# FPGA_NonIO.net
KiCad netlist of a schematic drawn in Altium Designer
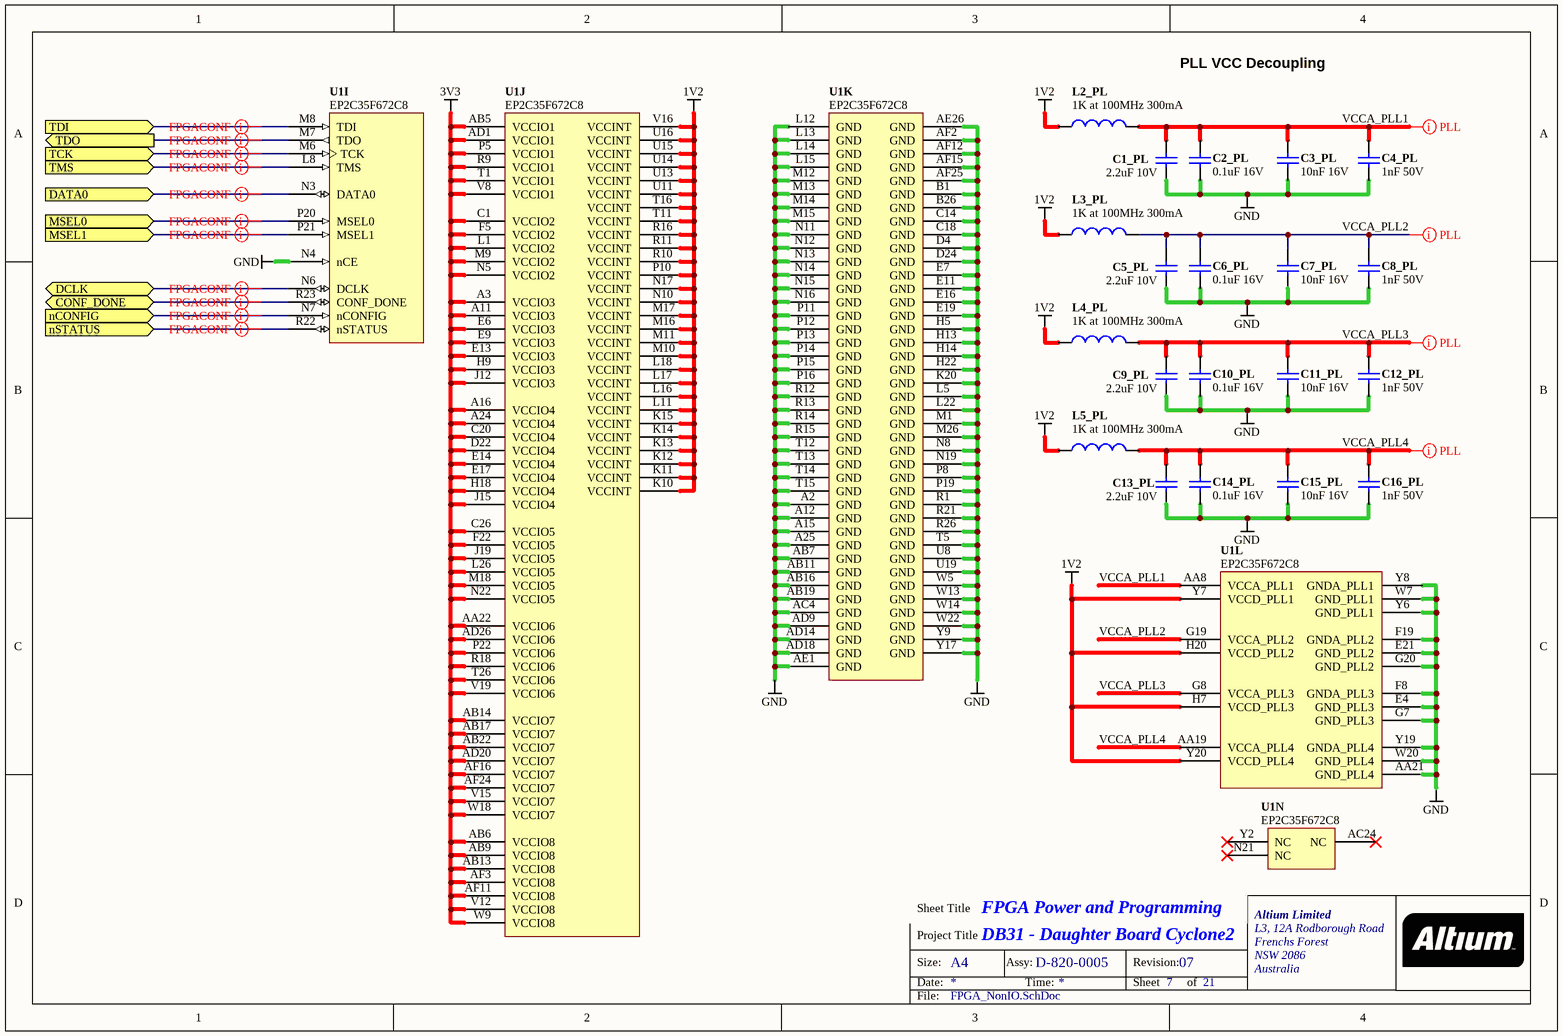
[diagram p0: FPGA_NonIO.SchDoc]

(export (version "E")
  (design (tool "Eeschema 10.0.6"))
  (components
    (comp (ref "C1_PL")
      (value "2.2uF 10V")
      (footprint "CAPC1608-STAR")
      (description "Capacitor, Ceramic, 2.2uF 10% 10V 0603 (1608) X5R")
      (fields (field (name "TOLERANCE") "10 %"))
      (libsource (lib "AltiumDesignLibrary") (part "CAP-NP"))
    )
    (comp (ref "C2_PL")
      (value "0.1uF 16V")
      (footprint "CAPC1005-STAR")
      (description "Capacitor, Ceramic, 0.1uF 10% 16V 0402 (1005) X7R")
      (fields (field (name "TOLERANCE") "10 %"))
      (libsource (lib "AltiumDesignLibrary") (part "CAP-NP"))
    )
    (comp (ref "C3_PL")
      (value "10nF 16V")
      (footprint "CAPC1005-STAR")
      (description "Capacitor, Ceramic, 10nF 10% 16V 0402 (1005) X7R")
      (fields (field (name "TOLERANCE") "10 %"))
      (libsource (lib "AltiumDesignLibrary") (part "CAP-NP"))
    )
    (comp (ref "C4_PL")
      (value "1nF 50V")
      (footprint "CAPC1005-STAR")
      (description "Capacitor, Ceramic, 1nF 10% 50V 0402 (1005) X7R")
      (fields (field (name "TOLERANCE") "10 %"))
      (libsource (lib "AltiumDesignLibrary") (part "CAP-NP"))
    )
    (comp (ref "C5_PL")
      (value "2.2uF 10V")
      (footprint "CAPC1608-STAR")
      (description "Capacitor, Ceramic, 2.2uF 10% 10V 0603 (1608) X5R")
      (fields (field (name "TOLERANCE") "10 %"))
      (libsource (lib "AltiumDesignLibrary") (part "CAP-NP"))
    )
    (comp (ref "C6_PL")
      (value "0.1uF 16V")
      (footprint "CAPC1005-STAR")
      (description "Capacitor, Ceramic, 0.1uF 10% 16V 0402 (1005) X7R")
      (fields (field (name "TOLERANCE") "10 %"))
      (libsource (lib "AltiumDesignLibrary") (part "CAP-NP"))
    )
    (comp (ref "C7_PL")
      (value "10nF 16V")
      (footprint "CAPC1005-STAR")
      (description "Capacitor, Ceramic, 10nF 10% 16V 0402 (1005) X7R")
      (fields (field (name "TOLERANCE") "10 %"))
      (libsource (lib "AltiumDesignLibrary") (part "CAP-NP"))
    )
    (comp (ref "C8_PL")
      (value "1nF 50V")
      (footprint "CAPC1005-STAR")
      (description "Capacitor, Ceramic, 1nF 10% 50V 0402 (1005) X7R")
      (fields (field (name "TOLERANCE") "10 %"))
      (libsource (lib "AltiumDesignLibrary") (part "CAP-NP"))
    )
    (comp (ref "C9_PL")
      (value "2.2uF 10V")
      (footprint "CAPC1608-STAR")
      (description "Capacitor, Ceramic, 2.2uF 10% 10V 0603 (1608) X5R")
      (fields (field (name "TOLERANCE") "10 %"))
      (libsource (lib "AltiumDesignLibrary") (part "CAP-NP"))
    )
    (comp (ref "C10_PL")
      (value "0.1uF 16V")
      (footprint "CAPC1005-STAR")
      (description "Capacitor, Ceramic, 0.1uF 10% 16V 0402 (1005) X7R")
      (fields (field (name "TOLERANCE") "10 %"))
      (libsource (lib "AltiumDesignLibrary") (part "CAP-NP"))
    )
    (comp (ref "C11_PL")
      (value "10nF 16V")
      (footprint "CAPC1005-STAR")
      (description "Capacitor, Ceramic, 10nF 10% 16V 0402 (1005) X7R")
      (fields (field (name "TOLERANCE") "10 %"))
      (libsource (lib "AltiumDesignLibrary") (part "CAP-NP"))
    )
    (comp (ref "C12_PL")
      (value "1nF 50V")
      (footprint "CAPC1005-STAR")
      (description "Capacitor, Ceramic, 1nF 10% 50V 0402 (1005) X7R")
      (fields (field (name "TOLERANCE") "10 %"))
      (libsource (lib "AltiumDesignLibrary") (part "CAP-NP"))
    )
    (comp (ref "C13_PL")
      (value "2.2uF 10V")
      (footprint "CAPC1608-STAR")
      (description "Capacitor, Ceramic, 2.2uF 10% 10V 0603 (1608) X5R")
      (fields (field (name "TOLERANCE") "10 %"))
      (libsource (lib "AltiumDesignLibrary") (part "CAP-NP"))
    )
    (comp (ref "C14_PL")
      (value "0.1uF 16V")
      (footprint "CAPC1005-STAR")
      (description "Capacitor, Ceramic, 0.1uF 10% 16V 0402 (1005) X7R")
      (fields (field (name "TOLERANCE") "10 %"))
      (libsource (lib "AltiumDesignLibrary") (part "CAP-NP"))
    )
    (comp (ref "C15_PL")
      (value "10nF 16V")
      (footprint "CAPC1005-STAR")
      (description "Capacitor, Ceramic, 10nF 10% 16V 0402 (1005) X7R")
      (fields (field (name "TOLERANCE") "10 %"))
      (libsource (lib "AltiumDesignLibrary") (part "CAP-NP"))
    )
    (comp (ref "C16_PL")
      (value "1nF 50V")
      (footprint "CAPC1005-STAR")
      (description "Capacitor, Ceramic, 1nF 10% 50V 0402 (1005) X7R")
      (fields (field (name "TOLERANCE") "10 %"))
      (libsource (lib "AltiumDesignLibrary") (part "CAP-NP"))
    )
    (comp (ref "L2_PL")
      (value "1K at 100MHz 300mA")
      (footprint "INDC2012-STAR")
      (description "Inductor, Ferrite Bead 1K@100MHz 300mA 0805 (2012) BMB2A1000LN2")
      (libsource (lib "AltiumDesignLibrary") (part "IND-FER"))
    )
    (comp (ref "L3_PL")
      (value "1K at 100MHz 300mA")
      (footprint "INDC2012-STAR")
      (description "Inductor, Ferrite Bead 1K@100MHz 300mA 0805 (2012) BMB2A1000LN2")
      (libsource (lib "AltiumDesignLibrary") (part "IND-FER"))
    )
    (comp (ref "L4_PL")
      (value "1K at 100MHz 300mA")
      (footprint "INDC2012-STAR")
      (description "Inductor, Ferrite Bead 1K@100MHz 300mA 0805 (2012) BMB2A1000LN2")
      (libsource (lib "AltiumDesignLibrary") (part "IND-FER"))
    )
    (comp (ref "L5_PL")
      (value "1K at 100MHz 300mA")
      (footprint "INDC2012-STAR")
      (description "Inductor, Ferrite Bead 1K@100MHz 300mA 0805 (2012) BMB2A1000LN2")
      (libsource (lib "AltiumDesignLibrary") (part "IND-FER"))
    )
    (comp (ref "U1")
      (value "EP2C35F672C8")
      (footprint "BGA100P26X26-672")
      (description "FPGA, Altera Cyclone2-35 F672")
      (libsource (lib "AltiumDesignLibrary") (part "EP2C35F672C8"))
    )
  )
  (nets
    (net (code "1") (name "/CONF_DONE") (class "Default")
      (node (ref "U1") (pin "R23") (pinfunction "CONF_DONE_R23") (pintype "bidirectional"))
    )
    (net (code "2") (name "/DATA0") (class "Default")
      (node (ref "U1") (pin "N3") (pinfunction "DATA0_N3") (pintype "bidirectional"))
    )
    (net (code "3") (name "/DCLK") (class "Default")
      (node (ref "U1") (pin "N6") (pinfunction "DCLK_N6") (pintype "bidirectional"))
    )
    (net (code "4") (name "/MSEL0") (class "Default")
      (node (ref "U1") (pin "P20") (pinfunction "MSEL0_P20") (pintype "input"))
    )
    (net (code "5") (name "/MSEL1") (class "Default")
      (node (ref "U1") (pin "P21") (pinfunction "MSEL1_P21") (pintype "input"))
    )
    (net (code "6") (name "/TCK") (class "Default")
      (node (ref "U1") (pin "M6") (pinfunction "TCK_M6") (pintype "input"))
    )
    (net (code "7") (name "/TDI") (class "Default")
      (node (ref "U1") (pin "M8") (pinfunction "TDI_M8") (pintype "input"))
    )
    (net (code "8") (name "/TDO") (class "Default")
      (node (ref "U1") (pin "M7") (pinfunction "TDO_M7") (pintype "output"))
    )
    (net (code "9") (name "/TMS") (class "Default")
      (node (ref "U1") (pin "L8") (pinfunction "TMS_L8") (pintype "input"))
    )
    (net (code "10") (name "/VCCA_PLL1") (class "Default")
      (node (ref "C1_PL") (pin "1") (pinfunction "1_1") (pintype "passive"))
      (node (ref "C2_PL") (pin "1") (pinfunction "1_1") (pintype "passive"))
      (node (ref "C3_PL") (pin "1") (pinfunction "1_1") (pintype "passive"))
      (node (ref "C4_PL") (pin "1") (pinfunction "1_1") (pintype "passive"))
      (node (ref "L2_PL") (pin "2") (pinfunction "2_2") (pintype "passive"))
      (node (ref "U1") (pin "AA8") (pinfunction "VCCA_PLL1_AA8") (pintype "power_in"))
    )
    (net (code "11") (name "/VCCA_PLL2") (class "Default")
      (node (ref "C5_PL") (pin "1") (pinfunction "1_1") (pintype "passive"))
      (node (ref "C6_PL") (pin "1") (pinfunction "1_1") (pintype "passive"))
      (node (ref "C7_PL") (pin "1") (pinfunction "1_1") (pintype "passive"))
      (node (ref "C8_PL") (pin "1") (pinfunction "1_1") (pintype "passive"))
      (node (ref "L3_PL") (pin "2") (pinfunction "2_2") (pintype "passive"))
      (node (ref "U1") (pin "G19") (pinfunction "VCCA_PLL2_G19") (pintype "power_in"))
    )
    (net (code "12") (name "/VCCA_PLL3") (class "Default")
      (node (ref "C10_PL") (pin "1") (pinfunction "1_1") (pintype "passive"))
      (node (ref "C11_PL") (pin "1") (pinfunction "1_1") (pintype "passive"))
      (node (ref "C12_PL") (pin "1") (pinfunction "1_1") (pintype "passive"))
      (node (ref "C9_PL") (pin "1") (pinfunction "1_1") (pintype "passive"))
      (node (ref "L4_PL") (pin "2") (pinfunction "2_2") (pintype "passive"))
      (node (ref "U1") (pin "G8") (pinfunction "VCCA_PLL3_G8") (pintype "power_in"))
    )
    (net (code "13") (name "/VCCA_PLL4") (class "Default")
      (node (ref "C13_PL") (pin "1") (pinfunction "1_1") (pintype "passive"))
      (node (ref "C14_PL") (pin "1") (pinfunction "1_1") (pintype "passive"))
      (node (ref "C15_PL") (pin "1") (pinfunction "1_1") (pintype "passive"))
      (node (ref "C16_PL") (pin "1") (pinfunction "1_1") (pintype "passive"))
      (node (ref "L5_PL") (pin "2") (pinfunction "2_2") (pintype "passive"))
      (node (ref "U1") (pin "AA19") (pinfunction "VCCA_PLL4_AA19") (pintype "power_in"))
    )
    (net (code "14") (name "/nCONFIG") (class "Default")
      (node (ref "U1") (pin "N7") (pinfunction "nCONFIG_N7") (pintype "input"))
    )
    (net (code "15") (name "/nSTATUS") (class "Default")
      (node (ref "U1") (pin "R22") (pinfunction "nSTATUS_R22") (pintype "bidirectional"))
    )
    (net (code "16") (name "1V2") (class "Default")
      (node (ref "L2_PL") (pin "1") (pinfunction "1_1") (pintype "passive"))
      (node (ref "L3_PL") (pin "1") (pinfunction "1_1") (pintype "passive"))
      (node (ref "L4_PL") (pin "1") (pinfunction "1_1") (pintype "passive"))
      (node (ref "L5_PL") (pin "1") (pinfunction "1_1") (pintype "passive"))
      (node (ref "U1") (pin "H20") (pinfunction "VCCD_PLL2_H20") (pintype "power_in"))
      (node (ref "U1") (pin "H7") (pinfunction "VCCD_PLL3_H7") (pintype "power_in"))
      (node (ref "U1") (pin "K10") (pinfunction "VCCINT_K10") (pintype "power_in"))
      (node (ref "U1") (pin "K11") (pinfunction "VCCINT_K11") (pintype "power_in"))
      (node (ref "U1") (pin "K12") (pinfunction "VCCINT_K12") (pintype "power_in"))
      (node (ref "U1") (pin "K13") (pinfunction "VCCINT_K13") (pintype "power_in"))
      (node (ref "U1") (pin "K14") (pinfunction "VCCINT_K14") (pintype "power_in"))
      (node (ref "U1") (pin "K15") (pinfunction "VCCINT_K15") (pintype "power_in"))
      (node (ref "U1") (pin "L11") (pinfunction "VCCINT_L11") (pintype "power_in"))
      (node (ref "U1") (pin "L16") (pinfunction "VCCINT_L16") (pintype "power_in"))
      (node (ref "U1") (pin "L17") (pinfunction "VCCINT_L17") (pintype "power_in"))
      (node (ref "U1") (pin "L18") (pinfunction "VCCINT_L18") (pintype "power_in"))
      (node (ref "U1") (pin "M10") (pinfunction "VCCINT_M10") (pintype "power_in"))
      (node (ref "U1") (pin "M11") (pinfunction "VCCINT_M11") (pintype "power_in"))
      (node (ref "U1") (pin "M16") (pinfunction "VCCINT_M16") (pintype "power_in"))
      (node (ref "U1") (pin "M17") (pinfunction "VCCINT_M17") (pintype "power_in"))
      (node (ref "U1") (pin "N10") (pinfunction "VCCINT_N10") (pintype "power_in"))
      (node (ref "U1") (pin "N17") (pinfunction "VCCINT_N17") (pintype "power_in"))
      (node (ref "U1") (pin "P10") (pinfunction "VCCINT_P10") (pintype "power_in"))
      (node (ref "U1") (pin "R10") (pinfunction "VCCINT_R10") (pintype "power_in"))
      (node (ref "U1") (pin "R11") (pinfunction "VCCINT_R11") (pintype "power_in"))
      (node (ref "U1") (pin "R16") (pinfunction "VCCINT_R16") (pintype "power_in"))
      (node (ref "U1") (pin "T11") (pinfunction "VCCINT_T11") (pintype "power_in"))
      (node (ref "U1") (pin "T16") (pinfunction "VCCINT_T16") (pintype "power_in"))
      (node (ref "U1") (pin "U11") (pinfunction "VCCINT_U11") (pintype "power_in"))
      (node (ref "U1") (pin "U13") (pinfunction "VCCINT_U13") (pintype "power_in"))
      (node (ref "U1") (pin "U14") (pinfunction "VCCINT_U14") (pintype "power_in"))
      (node (ref "U1") (pin "U15") (pinfunction "VCCINT_U15") (pintype "power_in"))
      (node (ref "U1") (pin "U16") (pinfunction "VCCINT_U16") (pintype "power_in"))
      (node (ref "U1") (pin "V16") (pinfunction "VCCINT_V16") (pintype "power_in"))
      (node (ref "U1") (pin "Y20") (pinfunction "VCCD_PLL4_Y20") (pintype "power_in"))
      (node (ref "U1") (pin "Y7") (pinfunction "VCCD_PLL1_Y7") (pintype "power_in"))
    )
    (net (code "17") (name "3V3") (class "Default")
      (node (ref "U1") (pin "A11") (pinfunction "VCCIO3_A11") (pintype "power_in"))
      (node (ref "U1") (pin "A16") (pinfunction "VCCIO4_A16") (pintype "power_in"))
      (node (ref "U1") (pin "A24") (pinfunction "VCCIO4_A24") (pintype "power_in"))
      (node (ref "U1") (pin "A3") (pinfunction "VCCIO3_A3") (pintype "power_in"))
      (node (ref "U1") (pin "AA22") (pinfunction "VCCIO6_AA22") (pintype "power_in"))
      (node (ref "U1") (pin "AB13") (pinfunction "VCCIO8_AB13") (pintype "power_in"))
      (node (ref "U1") (pin "AB14") (pinfunction "VCCIO7_AB14") (pintype "power_in"))
      (node (ref "U1") (pin "AB17") (pinfunction "VCCIO7_AB17") (pintype "power_in"))
      (node (ref "U1") (pin "AB22") (pinfunction "VCCIO7_AB22") (pintype "power_in"))
      (node (ref "U1") (pin "AB5") (pinfunction "VCCIO1_AB5") (pintype "power_in"))
      (node (ref "U1") (pin "AB6") (pinfunction "VCCIO8_AB6") (pintype "power_in"))
      (node (ref "U1") (pin "AB9") (pinfunction "VCCIO8_AB9") (pintype "power_in"))
      (node (ref "U1") (pin "AD1") (pinfunction "VCCIO1_AD1") (pintype "power_in"))
      (node (ref "U1") (pin "AD20") (pinfunction "VCCIO7_AD20") (pintype "power_in"))
      (node (ref "U1") (pin "AD26") (pinfunction "VCCIO6_AD26") (pintype "power_in"))
      (node (ref "U1") (pin "AF11") (pinfunction "VCCIO8_AF11") (pintype "power_in"))
      (node (ref "U1") (pin "AF16") (pinfunction "VCCIO7_AF16") (pintype "power_in"))
      (node (ref "U1") (pin "AF24") (pinfunction "VCCIO7_AF24") (pintype "power_in"))
      (node (ref "U1") (pin "AF3") (pinfunction "VCCIO8_AF3") (pintype "power_in"))
      (node (ref "U1") (pin "C1") (pinfunction "VCCIO2_C1") (pintype "power_in"))
      (node (ref "U1") (pin "C20") (pinfunction "VCCIO4_C20") (pintype "power_in"))
      (node (ref "U1") (pin "C26") (pinfunction "VCCIO5_C26") (pintype "power_in"))
      (node (ref "U1") (pin "D22") (pinfunction "VCCIO4_D22") (pintype "power_in"))
      (node (ref "U1") (pin "E13") (pinfunction "VCCIO3_E13") (pintype "power_in"))
      (node (ref "U1") (pin "E14") (pinfunction "VCCIO4_E14") (pintype "power_in"))
      (node (ref "U1") (pin "E17") (pinfunction "VCCIO4_E17") (pintype "power_in"))
      (node (ref "U1") (pin "E6") (pinfunction "VCCIO3_E6") (pintype "power_in"))
      (node (ref "U1") (pin "E9") (pinfunction "VCCIO3_E9") (pintype "power_in"))
      (node (ref "U1") (pin "F22") (pinfunction "VCCIO5_F22") (pintype "power_in"))
      (node (ref "U1") (pin "F5") (pinfunction "VCCIO2_F5") (pintype "power_in"))
      (node (ref "U1") (pin "H18") (pinfunction "VCCIO4_H18") (pintype "power_in"))
      (node (ref "U1") (pin "H9") (pinfunction "VCCIO3_H9") (pintype "power_in"))
      (node (ref "U1") (pin "J12") (pinfunction "VCCIO3_J12") (pintype "power_in"))
      (node (ref "U1") (pin "J15") (pinfunction "VCCIO4_J15") (pintype "power_in"))
      (node (ref "U1") (pin "J19") (pinfunction "VCCIO5_J19") (pintype "power_in"))
      (node (ref "U1") (pin "L1") (pinfunction "VCCIO2_L1") (pintype "power_in"))
      (node (ref "U1") (pin "L26") (pinfunction "VCCIO5_L26") (pintype "power_in"))
      (node (ref "U1") (pin "M18") (pinfunction "VCCIO5_M18") (pintype "power_in"))
      (node (ref "U1") (pin "M9") (pinfunction "VCCIO2_M9") (pintype "power_in"))
      (node (ref "U1") (pin "N22") (pinfunction "VCCIO5_N22") (pintype "power_in"))
      (node (ref "U1") (pin "N5") (pinfunction "VCCIO2_N5") (pintype "power_in"))
      (node (ref "U1") (pin "P22") (pinfunction "VCCIO6_P22") (pintype "power_in"))
      (node (ref "U1") (pin "P5") (pinfunction "VCCIO1_P5") (pintype "power_in"))
      (node (ref "U1") (pin "R18") (pinfunction "VCCIO6_R18") (pintype "power_in"))
      (node (ref "U1") (pin "R9") (pinfunction "VCCIO1_R9") (pintype "power_in"))
      (node (ref "U1") (pin "T1") (pinfunction "VCCIO1_T1") (pintype "power_in"))
      (node (ref "U1") (pin "T26") (pinfunction "VCCIO6_T26") (pintype "power_in"))
      (node (ref "U1") (pin "V12") (pinfunction "VCCIO8_V12") (pintype "power_in"))
      (node (ref "U1") (pin "V15") (pinfunction "VCCIO7_V15") (pintype "power_in"))
      (node (ref "U1") (pin "V19") (pinfunction "VCCIO6_V19") (pintype "power_in"))
      (node (ref "U1") (pin "V8") (pinfunction "VCCIO1_V8") (pintype "power_in"))
      (node (ref "U1") (pin "W18") (pinfunction "VCCIO7_W18") (pintype "power_in"))
      (node (ref "U1") (pin "W9") (pinfunction "VCCIO8_W9") (pintype "power_in"))
    )
    (net (code "18") (name "GND") (class "Default")
      (node (ref "C10_PL") (pin "2") (pinfunction "2_2") (pintype "passive"))
      (node (ref "C11_PL") (pin "2") (pinfunction "2_2") (pintype "passive"))
      (node (ref "C12_PL") (pin "2") (pinfunction "2_2") (pintype "passive"))
      (node (ref "C13_PL") (pin "2") (pinfunction "2_2") (pintype "passive"))
      (node (ref "C14_PL") (pin "2") (pinfunction "2_2") (pintype "passive"))
      (node (ref "C15_PL") (pin "2") (pinfunction "2_2") (pintype "passive"))
      (node (ref "C16_PL") (pin "2") (pinfunction "2_2") (pintype "passive"))
      (node (ref "C1_PL") (pin "2") (pinfunction "2_2") (pintype "passive"))
      (node (ref "C2_PL") (pin "2") (pinfunction "2_2") (pintype "passive"))
      (node (ref "C3_PL") (pin "2") (pinfunction "2_2") (pintype "passive"))
      (node (ref "C4_PL") (pin "2") (pinfunction "2_2") (pintype "passive"))
      (node (ref "C5_PL") (pin "2") (pinfunction "2_2") (pintype "passive"))
      (node (ref "C6_PL") (pin "2") (pinfunction "2_2") (pintype "passive"))
      (node (ref "C7_PL") (pin "2") (pinfunction "2_2") (pintype "passive"))
      (node (ref "C8_PL") (pin "2") (pinfunction "2_2") (pintype "passive"))
      (node (ref "C9_PL") (pin "2") (pinfunction "2_2") (pintype "passive"))
      (node (ref "U1") (pin "A12") (pinfunction "GND_A12") (pintype "power_in"))
      (node (ref "U1") (pin "A15") (pinfunction "GND_A15") (pintype "power_in"))
      (node (ref "U1") (pin "A2") (pinfunction "GND_A2") (pintype "power_in"))
      (node (ref "U1") (pin "A25") (pinfunction "GND_A25") (pintype "power_in"))
      (node (ref "U1") (pin "AA21") (pinfunction "GND_PLL4_AA21") (pintype "power_in"))
      (node (ref "U1") (pin "AB11") (pinfunction "GND_AB11") (pintype "power_in"))
      (node (ref "U1") (pin "AB16") (pinfunction "GND_AB16") (pintype "power_in"))
      (node (ref "U1") (pin "AB19") (pinfunction "GND_AB19") (pintype "power_in"))
      (node (ref "U1") (pin "AB7") (pinfunction "GND_AB7") (pintype "power_in"))
      (node (ref "U1") (pin "AC4") (pinfunction "GND_AC4") (pintype "power_in"))
      (node (ref "U1") (pin "AD14") (pinfunction "GND_AD14") (pintype "power_in"))
      (node (ref "U1") (pin "AD18") (pinfunction "GND_AD18") (pintype "power_in"))
      (node (ref "U1") (pin "AD9") (pinfunction "GND_AD9") (pintype "power_in"))
      (node (ref "U1") (pin "AE1") (pinfunction "GND_AE1") (pintype "power_in"))
      (node (ref "U1") (pin "AE26") (pinfunction "GND_AE26") (pintype "power_in"))
      (node (ref "U1") (pin "AF12") (pinfunction "GND_AF12") (pintype "power_in"))
      (node (ref "U1") (pin "AF15") (pinfunction "GND_AF15") (pintype "power_in"))
      (node (ref "U1") (pin "AF2") (pinfunction "GND_AF2") (pintype "power_in"))
      (node (ref "U1") (pin "AF25") (pinfunction "GND_AF25") (pintype "power_in"))
      (node (ref "U1") (pin "B1") (pinfunction "GND_B1") (pintype "power_in"))
      (node (ref "U1") (pin "B26") (pinfunction "GND_B26") (pintype "power_in"))
      (node (ref "U1") (pin "C14") (pinfunction "GND_C14") (pintype "power_in"))
      (node (ref "U1") (pin "C18") (pinfunction "GND_C18") (pintype "power_in"))
      (node (ref "U1") (pin "D24") (pinfunction "GND_D24") (pintype "power_in"))
      (node (ref "U1") (pin "D4") (pinfunction "GND_D4") (pintype "power_in"))
      (node (ref "U1") (pin "E11") (pinfunction "GND_E11") (pintype "power_in"))
      (node (ref "U1") (pin "E16") (pinfunction "GND_E16") (pintype "power_in"))
      (node (ref "U1") (pin "E19") (pinfunction "GND_E19") (pintype "power_in"))
      (node (ref "U1") (pin "E21") (pinfunction "GND_PLL2_E21") (pintype "power_in"))
      (node (ref "U1") (pin "E4") (pinfunction "GND_PLL3_E4") (pintype "power_in"))
      (node (ref "U1") (pin "E7") (pinfunction "GND_E7") (pintype "power_in"))
      (node (ref "U1") (pin "F19") (pinfunction "GNDA_PLL2_F19") (pintype "power_in"))
      (node (ref "U1") (pin "F8") (pinfunction "GNDA_PLL3_F8") (pintype "power_in"))
      (node (ref "U1") (pin "G20") (pinfunction "GND_PLL2_G20") (pintype "power_in"))
      (node (ref "U1") (pin "G7") (pinfunction "GND_PLL3_G7") (pintype "power_in"))
      (node (ref "U1") (pin "H13") (pinfunction "GND_H13") (pintype "power_in"))
      (node (ref "U1") (pin "H14") (pinfunction "GND_H14") (pintype "power_in"))
      (node (ref "U1") (pin "H22") (pinfunction "GND_H22") (pintype "power_in"))
      (node (ref "U1") (pin "H5") (pinfunction "GND_H5") (pintype "power_in"))
      (node (ref "U1") (pin "K20") (pinfunction "GND_K20") (pintype "power_in"))
      (node (ref "U1") (pin "L12") (pinfunction "GND_L12") (pintype "power_in"))
      (node (ref "U1") (pin "L13") (pinfunction "GND_L13") (pintype "power_in"))
      (node (ref "U1") (pin "L14") (pinfunction "GND_L14") (pintype "power_in"))
      (node (ref "U1") (pin "L15") (pinfunction "GND_L15") (pintype "power_in"))
      (node (ref "U1") (pin "L22") (pinfunction "GND_L22") (pintype "power_in"))
      (node (ref "U1") (pin "L5") (pinfunction "GND_L5") (pintype "power_in"))
      (node (ref "U1") (pin "M1") (pinfunction "GND_M1") (pintype "power_in"))
      (node (ref "U1") (pin "M12") (pinfunction "GND_M12") (pintype "power_in"))
      (node (ref "U1") (pin "M13") (pinfunction "GND_M13") (pintype "power_in"))
      (node (ref "U1") (pin "M14") (pinfunction "GND_M14") (pintype "power_in"))
      (node (ref "U1") (pin "M15") (pinfunction "GND_M15") (pintype "power_in"))
      (node (ref "U1") (pin "M26") (pinfunction "GND_M26") (pintype "power_in"))
      (node (ref "U1") (pin "N11") (pinfunction "GND_N11") (pintype "power_in"))
      (node (ref "U1") (pin "N12") (pinfunction "GND_N12") (pintype "power_in"))
      (node (ref "U1") (pin "N13") (pinfunction "GND_N13") (pintype "power_in"))
      (node (ref "U1") (pin "N14") (pinfunction "GND_N14") (pintype "power_in"))
      (node (ref "U1") (pin "N15") (pinfunction "GND_N15") (pintype "power_in"))
      (node (ref "U1") (pin "N16") (pinfunction "GND_N16") (pintype "power_in"))
      (node (ref "U1") (pin "N19") (pinfunction "GND_N19") (pintype "power_in"))
      (node (ref "U1") (pin "N4") (pinfunction "nCE_N4") (pintype "input"))
      (node (ref "U1") (pin "N8") (pinfunction "GND_N8") (pintype "power_in"))
      (node (ref "U1") (pin "P11") (pinfunction "GND_P11") (pintype "power_in"))
      (node (ref "U1") (pin "P12") (pinfunction "GND_P12") (pintype "power_in"))
      (node (ref "U1") (pin "P13") (pinfunction "GND_P13") (pintype "power_in"))
      (node (ref "U1") (pin "P14") (pinfunction "GND_P14") (pintype "power_in"))
      (node (ref "U1") (pin "P15") (pinfunction "GND_P15") (pintype "power_in"))
      (node (ref "U1") (pin "P16") (pinfunction "GND_P16") (pintype "power_in"))
      (node (ref "U1") (pin "P19") (pinfunction "GND_P19") (pintype "power_in"))
      (node (ref "U1") (pin "P8") (pinfunction "GND_P8") (pintype "power_in"))
      (node (ref "U1") (pin "R1") (pinfunction "GND_R1") (pintype "power_in"))
      (node (ref "U1") (pin "R12") (pinfunction "GND_R12") (pintype "power_in"))
      (node (ref "U1") (pin "R13") (pinfunction "GND_R13") (pintype "power_in"))
      (node (ref "U1") (pin "R14") (pinfunction "GND_R14") (pintype "power_in"))
      (node (ref "U1") (pin "R15") (pinfunction "GND_R15") (pintype "power_in"))
      (node (ref "U1") (pin "R21") (pinfunction "GND_R21") (pintype "power_in"))
      (node (ref "U1") (pin "R26") (pinfunction "GND_R26") (pintype "power_in"))
      (node (ref "U1") (pin "T12") (pinfunction "GND_T12") (pintype "power_in"))
      (node (ref "U1") (pin "T13") (pinfunction "GND_T13") (pintype "power_in"))
      (node (ref "U1") (pin "T14") (pinfunction "GND_T14") (pintype "power_in"))
      (node (ref "U1") (pin "T15") (pinfunction "GND_T15") (pintype "power_in"))
      (node (ref "U1") (pin "T5") (pinfunction "GND_T5") (pintype "power_in"))
      (node (ref "U1") (pin "U19") (pinfunction "GND_U19") (pintype "power_in"))
      (node (ref "U1") (pin "U8") (pinfunction "GND_U8") (pintype "power_in"))
      (node (ref "U1") (pin "W13") (pinfunction "GND_W13") (pintype "power_in"))
      (node (ref "U1") (pin "W14") (pinfunction "GND_W14") (pintype "power_in"))
      (node (ref "U1") (pin "W20") (pinfunction "GND_PLL4_W20") (pintype "power_in"))
      (node (ref "U1") (pin "W22") (pinfunction "GND_W22") (pintype "power_in"))
      (node (ref "U1") (pin "W5") (pinfunction "GND_W5") (pintype "power_in"))
      (node (ref "U1") (pin "W7") (pinfunction "GND_PLL1_W7") (pintype "power_in"))
      (node (ref "U1") (pin "Y17") (pinfunction "GND_Y17") (pintype "power_in"))
      (node (ref "U1") (pin "Y19") (pinfunction "GNDA_PLL4_Y19") (pintype "power_in"))
      (node (ref "U1") (pin "Y6") (pinfunction "GND_PLL1_Y6") (pintype "power_in"))
      (node (ref "U1") (pin "Y8") (pinfunction "GNDA_PLL1_Y8") (pintype "power_in"))
      (node (ref "U1") (pin "Y9") (pinfunction "GND_Y9") (pintype "power_in"))
    )
    (net (code "19") (name "unconnected-(U1N-NC-PadAC24)") (class "Default")
      (node (ref "U1") (pin "AC24") (pinfunction "NC_AC24") (pintype "passive+no_connect"))
    )
    (net (code "20") (name "unconnected-(U1N-NC-PadN21)") (class "Default")
      (node (ref "U1") (pin "N21") (pinfunction "NC_N21") (pintype "passive+no_connect"))
    )
    (net (code "21") (name "unconnected-(U1N-NC-PadY2)") (class "Default")
      (node (ref "U1") (pin "Y2") (pinfunction "NC_Y2") (pintype "passive+no_connect"))
    )
  )
)
